# RadioIC.net
KiCad netlist of a schematic drawn in EAGLE
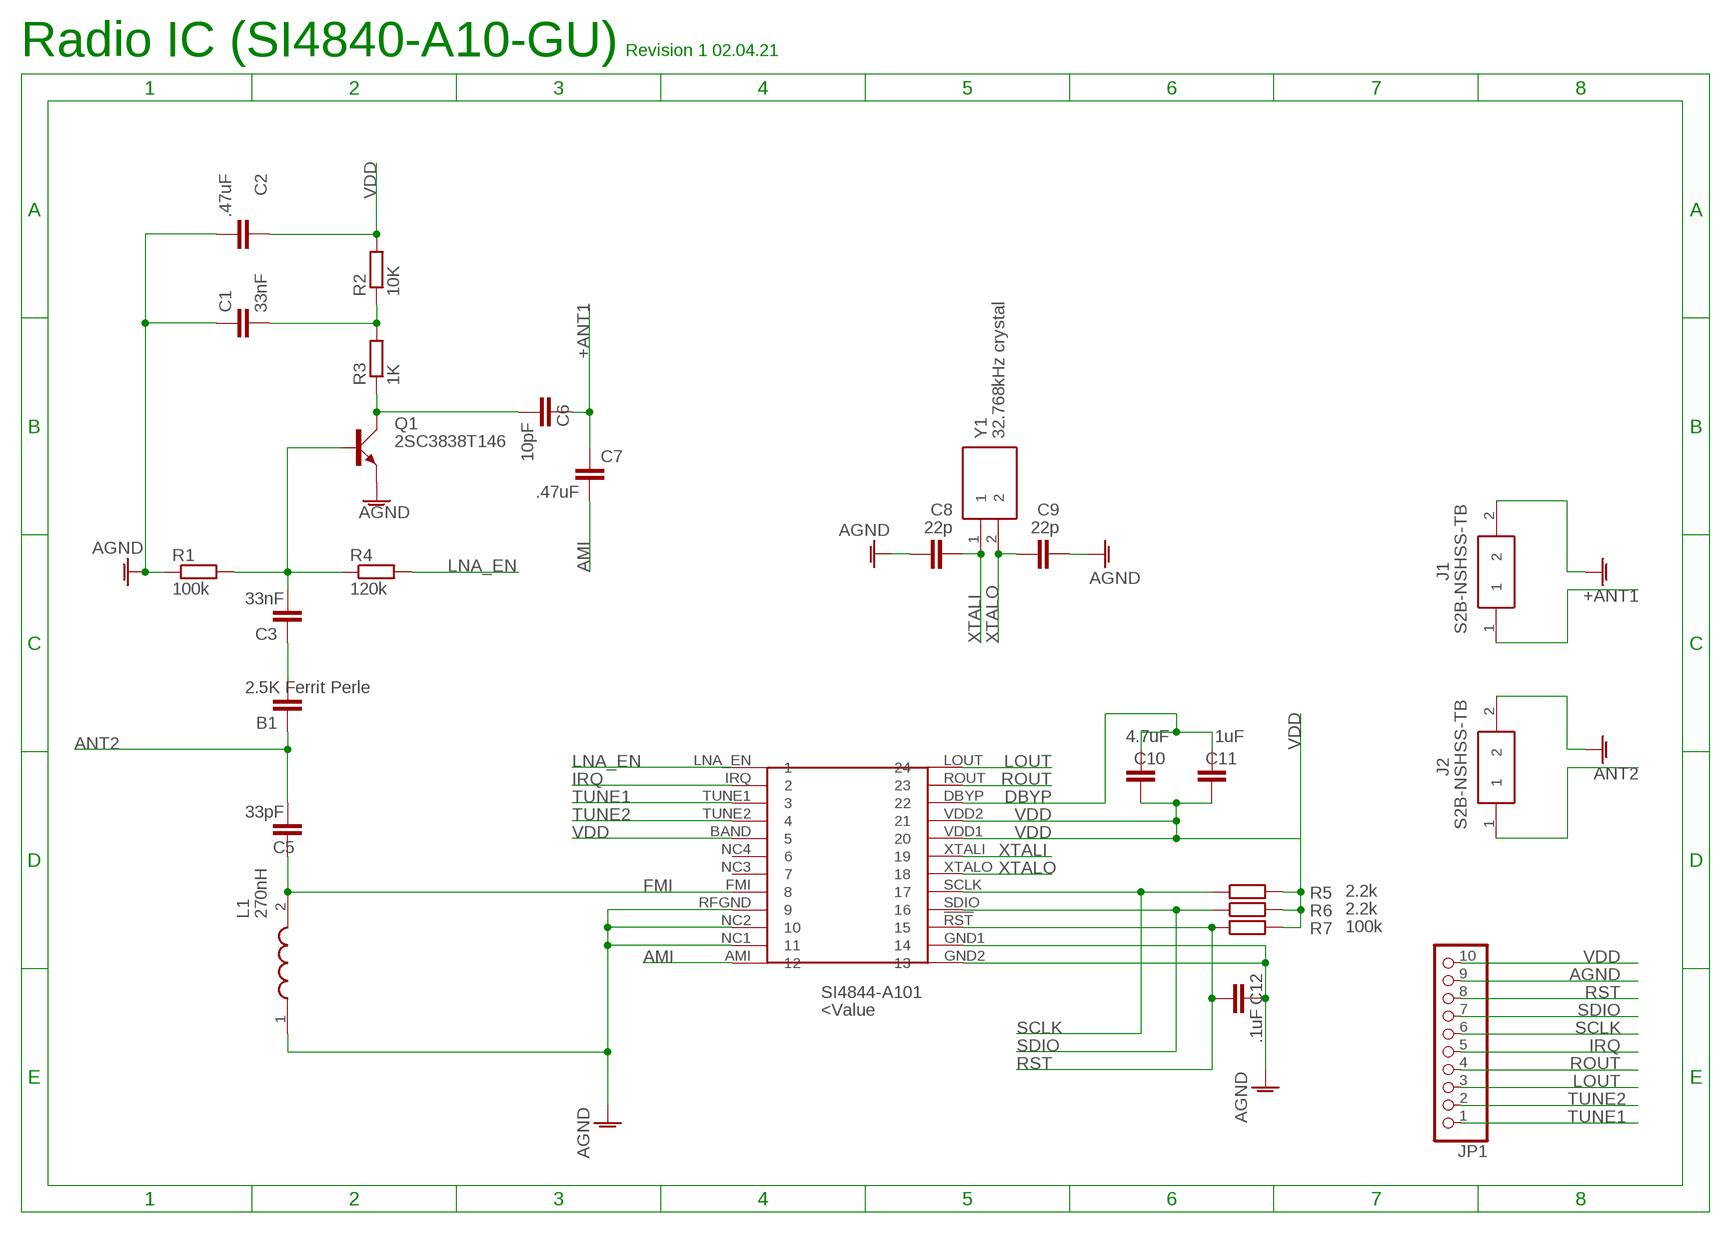
[diagram p0: schematic, sheet 1]

(export (version "E")
  (design (tool "Eeschema 10.0.6"))
  (components
    (comp (ref "B1")
      (value "2.5K Ferrit Perle")
      (footprint "eagle-import:C0805")
      (libsource (lib "eagle-import") (part "C-EU_805C0805"))
    )
    (comp (ref "C1")
      (value "33nF")
      (footprint "eagle-import:C1206")
      (libsource (lib "eagle-import") (part "CNC5L1X7R1C106K160AEC1206"))
    )
    (comp (ref "C2")
      (value ".47uF")
      (footprint "eagle-import:C0805")
      (libsource (lib "eagle-import") (part "C-EU_805C0805"))
    )
    (comp (ref "C3")
      (value "33nF")
      (footprint "eagle-import:C1206")
      (libsource (lib "eagle-import") (part "C-EU_1206C1206"))
    )
    (comp (ref "C5")
      (value "33pF")
      (footprint "eagle-import:C0805")
      (libsource (lib "eagle-import") (part "C-EU_805C0805"))
    )
    (comp (ref "C6")
      (value "10pF")
      (footprint "eagle-import:C0805")
      (libsource (lib "eagle-import") (part "C-EU_805C0805"))
    )
    (comp (ref "C7")
      (value ".47uF")
      (footprint "eagle-import:C0805")
      (libsource (lib "eagle-import") (part "C-EU_805C0805"))
    )
    (comp (ref "C8")
      (value "22p")
      (footprint "eagle-import:C0805")
      (libsource (lib "eagle-import") (part "C-EU_805C0805"))
    )
    (comp (ref "C9")
      (value "22p")
      (footprint "eagle-import:C0805")
      (libsource (lib "eagle-import") (part "C-EU_805C0805"))
    )
    (comp (ref "C10")
      (value "4.7uF")
      (footprint "eagle-import:C1206")
      (libsource (lib "eagle-import") (part "C-EU_1206C1206"))
    )
    (comp (ref "C11")
      (value "1uF")
      (footprint "eagle-import:C0805")
      (libsource (lib "eagle-import") (part "C-EU_805C0805"))
    )
    (comp (ref "C12")
      (value ".1uF")
      (footprint "eagle-import:C0805")
      (libsource (lib "eagle-import") (part "C-EU_805C0805"))
    )
    (comp (ref "J1")
      (value "S2B-NSHSS-TB")
      (footprint "eagle-import:SM02B-NSHSS-TB")
      (fields (field (name "MANUFACTURER_PART_NUMBER") "SM02B-NSHSS-TB(LF)(SN)"))
      (libsource (lib "eagle-import") (part "S2B-NSHSS-TB"))
    )
    (comp (ref "J2")
      (value "S2B-NSHSS-TB")
      (footprint "eagle-import:SM02B-NSHSS-TB")
      (fields (field (name "MANUFACTURER_PART_NUMBER") "SM02B-NSHSS-TB(LF)(SN)"))
      (libsource (lib "eagle-import") (part "S2B-NSHSS-TB"))
    )
    (comp (ref "JP1")
      (value "PINHD-1X10")
      (footprint "eagle-import:1X10")
      (libsource (lib "eagle-import") (part "PINHD-1X10"))
    )
    (comp (ref "L1")
      (value "270nH")
      (footprint "eagle-import:LQW2UAS12NG00L")
      (fields
        (field (name "MANUFACTURER_PART_NUMBER") "LQW2UASR56F0CL")
        (field (name "MOUSER_PART_NUMBER") "81-LQW2UASR56F0CL")
      )
      (libsource (lib "eagle-import") (part "LQW2UASR56F0CL"))
    )
    (comp (ref "Q1")
      (value "2SC3838T146")
      (footprint "eagle-import:SC59")
      (libsource (lib "eagle-import") (part "2SC3838T146"))
    )
    (comp (ref "R1")
      (value "100k")
      (footprint "eagle-import:R0805")
      (libsource (lib "eagle-import") (part "ERJ-PB6B5623VR0805"))
    )
    (comp (ref "R2")
      (value "10K")
      (footprint "eagle-import:R1206")
      (libsource (lib "eagle-import") (part "RCS1206100KJNEAR1206"))
    )
    (comp (ref "R3")
      (value "1K")
      (footprint "eagle-import:R1206")
      (libsource (lib "eagle-import") (part "RCS1206100KJNEAR1206"))
    )
    (comp (ref "R4")
      (value "120k")
      (footprint "eagle-import:R0805")
      (libsource (lib "eagle-import") (part "ERJ-PB6B5623VR0805"))
    )
    (comp (ref "R5")
      (value "2.2k")
      (footprint "eagle-import:R0805")
      (libsource (lib "eagle-import") (part "ERJ-PB6B5623VR0805"))
    )
    (comp (ref "R6")
      (value "2.2k")
      (footprint "eagle-import:R0805")
      (libsource (lib "eagle-import") (part "ERJ-PB6B5623VR0805"))
    )
    (comp (ref "R7")
      (value "100k")
      (footprint "eagle-import:R0805")
      (libsource (lib "eagle-import") (part "ERJ-PB6B5623VR0805"))
    )
    (comp (ref "SI4844-A101")
      (value "SI4840-A10-GU")
      (footprint "eagle-import:SSOP")
      (libsource (lib "eagle-import") (part "SI4840-A10-GU"))
    )
    (comp (ref "Y1")
      (value "32.768kHz crystal")
      (footprint "eagle-import:CM7VT1A32768KHZ125PF10PPMTBQC")
      (fields
        (field (name "MANUFACTURER_PART_NUMBER") "CM7V-T1A-32.768k-9pF-20PPM-TA-QA T3")
        (field (name "MOUSER_PART_NUMBER") "428-201568-MG03")
      )
      (libsource (lib "eagle-import") (part "CM7V-T1A-32.768K-9PF-20PPM-TA-"))
    )
  )
  (nets
    (net (code "1") (name "/+ANT1") (class "Default")
      (node (ref "C6") (pin "1") (pinfunction "1_1") (pintype "passive"))
      (node (ref "C7") (pin "1") (pinfunction "1_1") (pintype "passive"))
      (node (ref "J1") (pin "1") (pinfunction "1_1") (pintype "bidirectional"))
    )
    (net (code "2") (name "/AMI") (class "Default")
      (node (ref "C7") (pin "2") (pinfunction "2_2") (pintype "passive"))
      (node (ref "SI4844-A101") (pin "AMI") (pinfunction "12_AMI") (pintype "bidirectional"))
    )
    (net (code "3") (name "/ANT2") (class "Default")
      (node (ref "B1") (pin "1") (pinfunction "1_1") (pintype "passive"))
      (node (ref "C5") (pin "2") (pinfunction "2_2") (pintype "passive"))
      (node (ref "J2") (pin "1") (pinfunction "1_1") (pintype "bidirectional"))
    )
    (net (code "4") (name "/DBYP") (class "Default")
      (node (ref "C10") (pin "2") (pinfunction "2_2") (pintype "passive"))
      (node (ref "C11") (pin "2") (pinfunction "2_2") (pintype "passive"))
      (node (ref "SI4844-A101") (pin "DBYP") (pinfunction "22_DBYP") (pintype "bidirectional"))
    )
    (net (code "5") (name "/FMI") (class "Default")
      (node (ref "C5") (pin "1") (pinfunction "1_1") (pintype "passive"))
      (node (ref "L1") (pin "2") (pinfunction "2_2") (pintype "bidirectional"))
      (node (ref "SI4844-A101") (pin "FMI") (pinfunction "8_FMI") (pintype "bidirectional"))
    )
    (net (code "6") (name "/IRQ") (class "Default")
      (node (ref "JP1") (pin "5") (pinfunction "5_5") (pintype "passive"))
      (node (ref "SI4844-A101") (pin "IRQ") (pinfunction "2_IRQ") (pintype "bidirectional"))
    )
    (net (code "7") (name "/LNA_EN") (class "Default")
      (node (ref "R4") (pin "2") (pinfunction "2_2") (pintype "passive"))
      (node (ref "SI4844-A101") (pin "LNA_EN") (pinfunction "1_LNA_EN") (pintype "bidirectional"))
    )
    (net (code "8") (name "/LOUT") (class "Default")
      (node (ref "JP1") (pin "3") (pinfunction "3_3") (pintype "passive"))
      (node (ref "SI4844-A101") (pin "LOUT") (pinfunction "24_LOUT") (pintype "bidirectional"))
    )
    (net (code "9") (name "/ROUT") (class "Default")
      (node (ref "JP1") (pin "4") (pinfunction "4_4") (pintype "passive"))
      (node (ref "SI4844-A101") (pin "ROUT") (pinfunction "23_ROUT") (pintype "bidirectional"))
    )
    (net (code "10") (name "/RST") (class "Default")
      (node (ref "C12") (pin "2") (pinfunction "2_2") (pintype "passive"))
      (node (ref "JP1") (pin "8") (pinfunction "8_8") (pintype "passive"))
      (node (ref "R7") (pin "1") (pinfunction "1_1") (pintype "passive"))
      (node (ref "SI4844-A101") (pin "!RST") (pinfunction "15_!RST") (pintype "bidirectional"))
    )
    (net (code "11") (name "/SCLK") (class "Default")
      (node (ref "JP1") (pin "6") (pinfunction "6_6") (pintype "passive"))
      (node (ref "R5") (pin "1") (pinfunction "1_1") (pintype "passive"))
      (node (ref "SI4844-A101") (pin "SCLK") (pinfunction "17_SCLK") (pintype "bidirectional"))
    )
    (net (code "12") (name "/SDIO") (class "Default")
      (node (ref "JP1") (pin "7") (pinfunction "7_7") (pintype "passive"))
      (node (ref "R6") (pin "1") (pinfunction "1_1") (pintype "passive"))
      (node (ref "SI4844-A101") (pin "SDIO") (pinfunction "16_SDIO") (pintype "bidirectional"))
    )
    (net (code "13") (name "/TUNE1") (class "Default")
      (node (ref "JP1") (pin "1") (pinfunction "1_1") (pintype "passive"))
      (node (ref "SI4844-A101") (pin "TUNE1") (pinfunction "3_TUNE1") (pintype "bidirectional"))
    )
    (net (code "14") (name "/TUNE2") (class "Default")
      (node (ref "JP1") (pin "2") (pinfunction "2_2") (pintype "passive"))
      (node (ref "SI4844-A101") (pin "TUNE2") (pinfunction "4_TUNE2") (pintype "bidirectional"))
    )
    (net (code "15") (name "/VDD") (class "Default")
      (node (ref "C10") (pin "1") (pinfunction "1_1") (pintype "passive"))
      (node (ref "C11") (pin "1") (pinfunction "1_1") (pintype "passive"))
      (node (ref "C2") (pin "1") (pinfunction "1_1") (pintype "passive"))
      (node (ref "JP1") (pin "10") (pinfunction "10_10") (pintype "passive"))
      (node (ref "R2") (pin "2") (pinfunction "2_2") (pintype "passive"))
      (node (ref "R5") (pin "2") (pinfunction "2_2") (pintype "passive"))
      (node (ref "R6") (pin "2") (pinfunction "2_2") (pintype "passive"))
      (node (ref "R7") (pin "2") (pinfunction "2_2") (pintype "passive"))
      (node (ref "SI4844-A101") (pin "BAND") (pinfunction "5_BAND") (pintype "bidirectional"))
      (node (ref "SI4844-A101") (pin "VDD1") (pinfunction "20_VDD1") (pintype "power_in"))
      (node (ref "SI4844-A101") (pin "VDD2") (pinfunction "21_VDD2") (pintype "power_in"))
    )
    (net (code "16") (name "/XTALI") (class "Default")
      (node (ref "C8") (pin "2") (pinfunction "2_2") (pintype "passive"))
      (node (ref "SI4844-A101") (pin "XTALI") (pinfunction "19_XTALI") (pintype "bidirectional"))
      (node (ref "Y1") (pin "1") (pinfunction "1_1") (pintype "bidirectional"))
    )
    (net (code "17") (name "/XTALO") (class "Default")
      (node (ref "C9") (pin "1") (pinfunction "1_1") (pintype "passive"))
      (node (ref "SI4844-A101") (pin "XTALO") (pinfunction "18_XTALO") (pintype "bidirectional"))
      (node (ref "Y1") (pin "2") (pinfunction "2_2") (pintype "bidirectional"))
    )
    (net (code "18") (name "AGND") (class "Default")
      (node (ref "C1") (pin "1") (pinfunction "1_1") (pintype "passive"))
      (node (ref "C12") (pin "1") (pinfunction "1_1") (pintype "passive"))
      (node (ref "C2") (pin "2") (pinfunction "2_2") (pintype "passive"))
      (node (ref "C8") (pin "1") (pinfunction "1_1") (pintype "passive"))
      (node (ref "C9") (pin "2") (pinfunction "2_2") (pintype "passive"))
      (node (ref "J1") (pin "2") (pinfunction "2_2") (pintype "bidirectional"))
      (node (ref "J2") (pin "2") (pinfunction "2_2") (pintype "bidirectional"))
      (node (ref "JP1") (pin "9") (pinfunction "9_9") (pintype "passive"))
      (node (ref "L1") (pin "1") (pinfunction "1_1") (pintype "bidirectional"))
      (node (ref "Q1") (pin "E") (pinfunction "E_E") (pintype "passive"))
      (node (ref "R1") (pin "1") (pinfunction "1_1") (pintype "passive"))
      (node (ref "SI4844-A101") (pin "GND1") (pinfunction "14_GND1") (pintype "power_in"))
      (node (ref "SI4844-A101") (pin "GND2") (pinfunction "13_GND2") (pintype "power_in"))
      (node (ref "SI4844-A101") (pin "NC1") (pinfunction "11_NC1") (pintype "bidirectional"))
      (node (ref "SI4844-A101") (pin "NC2") (pinfunction "10_NC2") (pintype "bidirectional"))
      (node (ref "SI4844-A101") (pin "RFGND") (pinfunction "9_RFGND") (pintype "bidirectional"))
    )
    (net (code "19") (name "Net-(B1-Pad2)") (class "Default")
      (node (ref "B1") (pin "2") (pinfunction "2_2") (pintype "passive"))
      (node (ref "C3") (pin "1") (pinfunction "1_1") (pintype "passive"))
    )
    (net (code "20") (name "Net-(C1-Pad2)") (class "Default")
      (node (ref "C1") (pin "2") (pinfunction "2_2") (pintype "passive"))
      (node (ref "R2") (pin "1") (pinfunction "1_1") (pintype "passive"))
      (node (ref "R3") (pin "2") (pinfunction "2_2") (pintype "passive"))
    )
    (net (code "21") (name "Net-(C3-Pad2)") (class "Default")
      (node (ref "C3") (pin "2") (pinfunction "2_2") (pintype "passive"))
      (node (ref "Q1") (pin "B") (pinfunction "B_B") (pintype "passive"))
      (node (ref "R1") (pin "2") (pinfunction "2_2") (pintype "passive"))
      (node (ref "R4") (pin "1") (pinfunction "1_1") (pintype "passive"))
    )
    (net (code "22") (name "Net-(C6-Pad2)") (class "Default")
      (node (ref "C6") (pin "2") (pinfunction "2_2") (pintype "passive"))
      (node (ref "Q1") (pin "C") (pinfunction "C_C") (pintype "passive"))
      (node (ref "R3") (pin "1") (pinfunction "1_1") (pintype "passive"))
    )
    (net (code "23") (name "unconnected-(SI4844-A101-6-PadNC4)") (class "Default")
      (node (ref "SI4844-A101") (pin "NC4") (pinfunction "6_NC4") (pintype "bidirectional"))
    )
    (net (code "24") (name "unconnected-(SI4844-A101-7-PadNC3)") (class "Default")
      (node (ref "SI4844-A101") (pin "NC3") (pinfunction "7_NC3") (pintype "bidirectional"))
    )
  )
)
